# 2-Power.net
KiCad netlist of a schematic drawn in Altium Designer
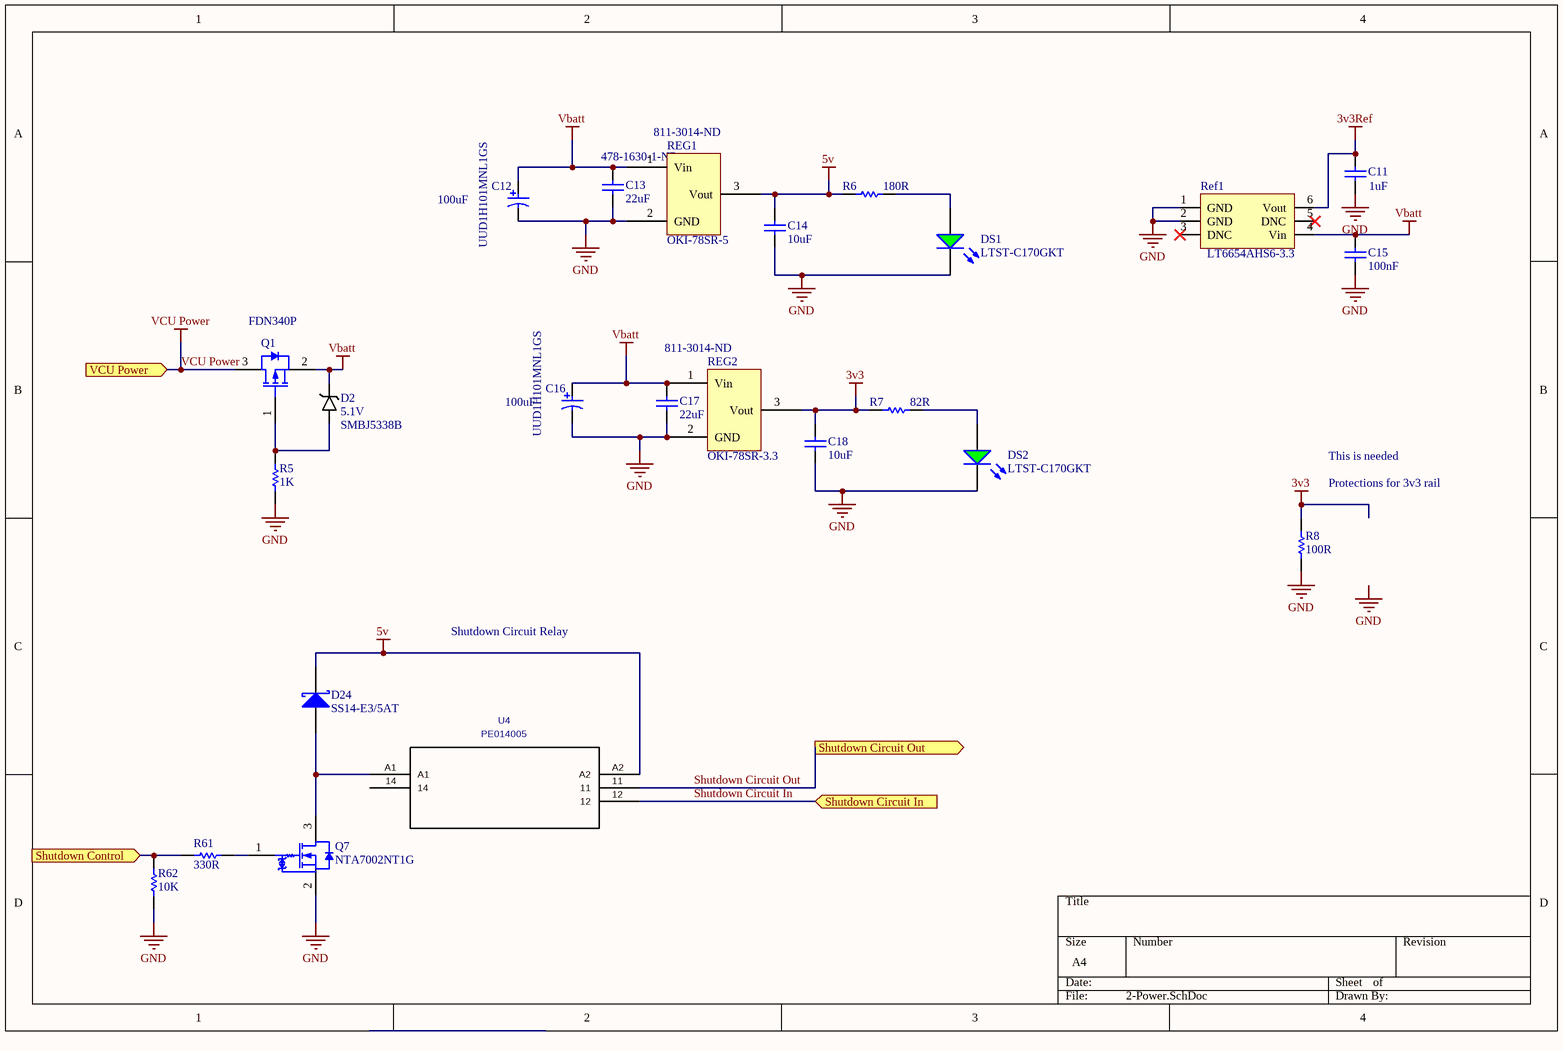
[diagram p0: 2-Power.SchDoc]

(export (version "E")
  (design (tool "Eeschema 10.0.6"))
  (components
    (comp (ref "C11")
      (value "1uF")
      (footprint "1608[0603]")
      (description "Capacitor")
      (fields
        (field (name "MANUFACTURER") "Murata Electronics North America")
        (field (name "MANUFACTURER PART NUMBER") "GRM188R61E105KA12D")
      )
      (libsource (lib "Miscellaneous Devices") (part "Cap"))
    )
    (comp (ref "C12")
      (value "UUD1H101MNL1GS")
      (footprint "NIC-CAPA2-8X10_V")
      (fields (field (name "MANUFACTURER") "Nichicon") (field (name "TOLERANCE") "±20%"))
      (libsource (lib "Altium Content Vault") (part "NIC-CAP-P-2"))
    )
    (comp (ref "C13")
      (value "22uF")
      (footprint "C1210_M")
      (description "Capacitor")
      (fields
        (field (name "MANUFACTURER") "Yageo")
        (field (name "MANUFACTURER PART NUMBER") "CC1210MKX5R8BB226")
        (field (name "SUPPLIER PART NUMBER 1") "478-1630-1-ND")
      )
      (libsource (lib "Miscellaneous Devices") (part "Cap"))
    )
    (comp (ref "C14")
      (value "10uF")
      (footprint "C1210_M")
      (description "Capacitor")
      (fields
        (field (name "MANUFACTURER") "Yageo")
        (field (name "MANUFACTURER PART NUMBER") "CC1210ZKY5V8BB106")
      )
      (libsource (lib "Miscellaneous Devices") (part "Cap"))
    )
    (comp (ref "C15")
      (value "100nF")
      (footprint "1608[0603]")
      (description "Capacitor")
      (fields
        (field (name "MANUFACTURER") "Yageo")
        (field (name "MANUFACTURER PART NUMBER") "CC0603KRX7R9BB104")
      )
      (libsource (lib "Miscellaneous Devices") (part "Cap"))
    )
    (comp (ref "C16")
      (value "UUD1H101MNL1GS")
      (footprint "NIC-CAPA2-8X10_V")
      (fields (field (name "MANUFACTURER") "Nichicon") (field (name "TOLERANCE") "±20%"))
      (libsource (lib "Altium Content Vault") (part "NIC-CAP-P-2"))
    )
    (comp (ref "C17")
      (value "22uF")
      (footprint "C1210_M")
      (description "Capacitor")
      (fields
        (field (name "MANUFACTURER") "Yageo")
        (field (name "MANUFACTURER PART NUMBER") "CC1210MKX5R8BB226")
      )
      (libsource (lib "Miscellaneous Devices") (part "Cap"))
    )
    (comp (ref "C18")
      (value "10uF")
      (footprint "C1210_M")
      (description "Capacitor")
      (fields
        (field (name "MANUFACTURER") "Yageo")
        (field (name "MANUFACTURER PART NUMBER") "CC1210ZKY5V8BB106")
      )
      (libsource (lib "Miscellaneous Devices") (part "Cap"))
    )
    (comp (ref "D2")
      (value "Zener Diode, 5.1V, 5W SMBJ5338B")
      (footprint "DO-214AA (SMB)")
      (fields
        (field (name "POWER") "5W")
        (field (name "REVERSE VOLTAGE") "5.1V")
        (field (name "PART NUMBER") "SMBJ5338B")
      )
      (libsource (lib "VCU Library") (part "Zener Diode, 5.1V, 5W SMBJ5338B"))
    )
    (comp (ref "D24")
      (value "SS14-E3/5AT")
      (footprint "VISH-DO-214AC-2_V")
      (fields (field (name "MANUFACTURER") "Vishay Semiconductor"))
      (libsource (lib "Altium Content Vault") (part "VISH-DSKY_A1K2-2"))
    )
    (comp (ref "DS1")
      (value "LTST-C170GKT")
      (footprint "LTST-C170GKT_V")
      (description "LED Uni-Color Green, 100 mW, 120 mA, -55 to 85 degC, 2-Pin SMD, RoHS, Tape and Reel")
      (fields (field (name "MANUFACTURER") "Lite-On"))
      (libsource (lib "Altium Content Vault") (part "LED-GREEN-AK-2"))
    )
    (comp (ref "DS2")
      (value "LTST-C170GKT")
      (footprint "LTST-C170GKT_V")
      (description "LED Uni-Color Green, 100 mW, 120 mA, -55 to 85 degC, 2-Pin SMD, RoHS, Tape and Reel")
      (fields (field (name "MANUFACTURER") "Lite-On"))
      (libsource (lib "Altium Content Vault") (part "LED-GREEN-AK-2"))
    )
    (comp (ref "Q1")
      (value "FDN340P")
      (footprint "FAIR-SSOT3L-3_V")
      (fields (field (name "MANUFACTURER") "Fairchild Semiconductor"))
      (libsource (lib "Altium Content Vault") (part "PEMOS-GSD-3"))
    )
    (comp (ref "Q7")
      (value "NTA7002NT1G")
      (footprint "ONSC-SC-75-3-463-01_V")
      (fields (field (name "MANUFACTURER") "On Semiconductor"))
      (libsource (lib "Altium Content Vault") (part "ONSC-NMOS-G1S2D3-3_D"))
    )
    (comp (ref "R5")
      (value "1K")
      (footprint "1608[0603]")
      (description "Resistor")
      (fields
        (field (name "MANUFACTURER") "Panasonic Electronic Components")
        (field (name "MANUFACTURER PART NUMBER") "ERJ-PA3F1001V")
      )
      (libsource (lib "Miscellaneous Devices") (part "Res1"))
    )
    (comp (ref "R6")
      (value "180R")
      (footprint "1608[0603]")
      (description "Resistor")
      (fields
        (field (name "MANUFACTURER") "Yageo")
        (field (name "MANUFACTURER PART NUMBER") "RC0603JR-07180RL")
      )
      (libsource (lib "Miscellaneous Devices") (part "Res1"))
    )
    (comp (ref "R7")
      (value "82R")
      (footprint "1608[0603]")
      (description "Resistor")
      (fields
        (field (name "MANUFACTURER") "Yageo")
        (field (name "MANUFACTURER PART NUMBER") "RC0603JR-0782RL")
      )
      (libsource (lib "Miscellaneous Devices") (part "Res1"))
    )
    (comp (ref "R8")
      (value "100R")
      (footprint "RESC1206(3216)_M")
      (description "100R 0.25W 5% 1206 (3216 Metric)  SMD")
      (fields (field (name "TOLERANCE") "5 %") (field (name "POWER") "0.25 W"))
      (libsource (lib "Altium Content Vault") (part "RES"))
    )
    (comp (ref "R61")
      (value "330R")
      (footprint "1608[0603]")
      (description "Resistor")
      (fields
        (field (name "MANUFACTURER") "Panasonic Electronic Components")
        (field (name "MANUFACTURER PART NUMBER") "ERJ-PA3F1001V")
      )
      (libsource (lib "Miscellaneous Devices") (part "Res1"))
    )
    (comp (ref "R62")
      (value "10K")
      (footprint "1608[0603]")
      (description "Resistor")
      (fields
        (field (name "MANUFACTURER") "Panasonic Electronic Components")
        (field (name "MANUFACTURER PART NUMBER") "ERJ-PA3F1001V")
      )
      (libsource (lib "Miscellaneous Devices") (part "Res1"))
    )
    (comp (ref "Ref1")
      (value "LT6654AHS6-3.3")
      (footprint "TSOT-23 S6")
      (fields
        (field (name "DIGIKEY PART NUMBER") "LT6654AHS6-3.3#TRMPBFCT-ND")
        (field (name "MANUFACTURER") "Linear Technology")
        (field (name "TOLERANCE") "±0.05%")
      )
      (libsource (lib "VCU Library") (part "LT6654AHS6-3.3"))
    )
    (comp (ref "REG1")
      (value "OKI-78SR-5")
      (footprint "OKI-78SR-5/1.5-W - Horizontal")
      (description "5V DCDC")
      (fields
        (field (name "SUPPLIER PART NUMBER 2") "811-3014-ND")
        (field (name "MANUFACTURER") "Murata Power Solutions Inc.")
        (field (name "MANUFACTURER PART NUMBER") "OKI-78SR-3.3/1.5-W36H-C")
      )
      (libsource (lib "FE Schem Lib") (part "OKI-78SR-5"))
    )
    (comp (ref "REG2")
      (value "OKI-78SR-3.3")
      (footprint "Reg - TH, 3 pin, 100 mil Pitch, VTL")
      (description "3.3V DCDC")
      (fields
        (field (name "SUPPLIER PART NUMBER 2") "811-3014-ND")
        (field (name "MANUFACTURER") "Murata Power Solutions Inc.")
        (field (name "MANUFACTURER PART NUMBER") "OKI-78SR-3.3/1.5-W36H-C")
      )
      (libsource (lib "FE Schem Lib") (part "OKI-78SR-5"))
    )
    (comp (ref "U4")
      (value "PE014005")
      (footprint "PE014005")
      (fields (field (name "COPYRIGHT") "Copyright (C) 2021 Ultra Librarian. All rights reserved."))
      (libsource (lib "AltiumV15") (part "PE014005"))
    )
  )
  (nets
    (net (code "1") (name "/Shutdown Circuit In") (class "Default")
      (node (ref "U4") (pin "12") (pinfunction "12_12") (pintype "passive"))
    )
    (net (code "2") (name "/Shutdown Circuit Out") (class "Default")
      (node (ref "U4") (pin "11") (pinfunction "11_11") (pintype "passive"))
    )
    (net (code "3") (name "/Shutdown Control") (class "Default")
      (node (ref "R61") (pin "2") (pinfunction "2_2") (pintype "passive"))
      (node (ref "R62") (pin "2") (pinfunction "2_2") (pintype "passive"))
    )
    (net (code "4") (name "3v3") (class "Default")
      (node (ref "C18") (pin "2") (pinfunction "2_2") (pintype "passive"))
      (node (ref "R7") (pin "1") (pinfunction "1_1") (pintype "passive"))
      (node (ref "R8") (pin "2") (pinfunction "2_2") (pintype "passive"))
      (node (ref "REG2") (pin "3") (pinfunction "Vout_3") (pintype "passive"))
    )
    (net (code "5") (name "3v3Ref") (class "Default")
      (node (ref "C11") (pin "2") (pinfunction "2_2") (pintype "passive"))
      (node (ref "Ref1") (pin "6") (pinfunction "Vout_6") (pintype "passive"))
    )
    (net (code "6") (name "5v") (class "Default")
      (node (ref "C14") (pin "2") (pinfunction "2_2") (pintype "passive"))
      (node (ref "D24") (pin "2") (pinfunction "K_2") (pintype "passive"))
      (node (ref "R6") (pin "1") (pinfunction "1_1") (pintype "passive"))
      (node (ref "REG1") (pin "3") (pinfunction "Vout_3") (pintype "passive"))
      (node (ref "U4") (pin "A2") (pinfunction "A2_A2") (pintype "passive"))
    )
    (net (code "7") (name "GND") (class "Default")
      (node (ref "C11") (pin "1") (pinfunction "1_1") (pintype "passive"))
      (node (ref "C12") (pin "2") (pinfunction "2_2") (pintype "passive"))
      (node (ref "C13") (pin "1") (pinfunction "1_1") (pintype "passive"))
      (node (ref "C14") (pin "1") (pinfunction "1_1") (pintype "passive"))
      (node (ref "C15") (pin "1") (pinfunction "1_1") (pintype "passive"))
      (node (ref "C16") (pin "2") (pinfunction "2_2") (pintype "passive"))
      (node (ref "C17") (pin "1") (pinfunction "1_1") (pintype "passive"))
      (node (ref "C18") (pin "1") (pinfunction "1_1") (pintype "passive"))
      (node (ref "DS1") (pin "2") (pinfunction "K_2") (pintype "passive"))
      (node (ref "DS2") (pin "2") (pinfunction "K_2") (pintype "passive"))
      (node (ref "Q7") (pin "2") (pinfunction "S_2") (pintype "passive"))
      (node (ref "R5") (pin "1") (pinfunction "1_1") (pintype "passive"))
      (node (ref "R62") (pin "1") (pinfunction "1_1") (pintype "passive"))
      (node (ref "R8") (pin "1") (pinfunction "1_1") (pintype "passive"))
      (node (ref "REG1") (pin "2") (pinfunction "GND_2") (pintype "passive"))
      (node (ref "REG2") (pin "2") (pinfunction "GND_2") (pintype "passive"))
      (node (ref "Ref1") (pin "1") (pinfunction "GND_1") (pintype "passive"))
      (node (ref "Ref1") (pin "2") (pinfunction "GND_2") (pintype "passive"))
    )
    (net (code "8") (name "Net-(D2-2)") (class "Default")
      (node (ref "D2") (pin "A") (pinfunction "2_A") (pintype "passive"))
      (node (ref "Q1") (pin "1") (pinfunction "GATE_1") (pintype "passive"))
      (node (ref "R5") (pin "2") (pinfunction "2_2") (pintype "passive"))
    )
    (net (code "9") (name "Net-(D24-A)") (class "Default")
      (node (ref "D24") (pin "1") (pinfunction "A_1") (pintype "passive"))
      (node (ref "Q7") (pin "3") (pinfunction "D_3") (pintype "passive"))
      (node (ref "U4") (pin "A1") (pinfunction "A1_A1") (pintype "passive"))
    )
    (net (code "10") (name "Net-(DS1-A)") (class "Default")
      (node (ref "DS1") (pin "1") (pinfunction "A_1") (pintype "passive"))
      (node (ref "R6") (pin "2") (pinfunction "2_2") (pintype "passive"))
    )
    (net (code "11") (name "Net-(DS2-A)") (class "Default")
      (node (ref "DS2") (pin "1") (pinfunction "A_1") (pintype "passive"))
      (node (ref "R7") (pin "2") (pinfunction "2_2") (pintype "passive"))
    )
    (net (code "12") (name "Net-(Q7-G)") (class "Default")
      (node (ref "Q7") (pin "1") (pinfunction "G_1") (pintype "passive"))
      (node (ref "R61") (pin "1") (pinfunction "1_1") (pintype "passive"))
    )
    (net (code "13") (name "VCU Power") (class "Default")
      (node (ref "Q1") (pin "3") (pinfunction "DRAIN_3") (pintype "passive"))
    )
    (net (code "14") (name "Vbatt") (class "Default")
      (node (ref "C12") (pin "1") (pinfunction "1_1") (pintype "passive"))
      (node (ref "C13") (pin "2") (pinfunction "2_2") (pintype "passive"))
      (node (ref "C15") (pin "2") (pinfunction "2_2") (pintype "passive"))
      (node (ref "C16") (pin "1") (pinfunction "1_1") (pintype "passive"))
      (node (ref "C17") (pin "2") (pinfunction "2_2") (pintype "passive"))
      (node (ref "D2") (pin "K") (pinfunction "1_K") (pintype "passive"))
      (node (ref "Q1") (pin "2") (pinfunction "SOURCE_2") (pintype "passive"))
      (node (ref "REG1") (pin "1") (pinfunction "Vin_1") (pintype "passive"))
      (node (ref "REG2") (pin "1") (pinfunction "Vin_1") (pintype "passive"))
      (node (ref "Ref1") (pin "4") (pinfunction "Vin_4") (pintype "passive"))
    )
    (net (code "15") (name "unconnected-(Ref1-DNC-Pad3)") (class "Default")
      (node (ref "Ref1") (pin "3") (pinfunction "DNC_3") (pintype "passive+no_connect"))
    )
    (net (code "16") (name "unconnected-(Ref1-DNC-Pad5)") (class "Default")
      (node (ref "Ref1") (pin "5") (pinfunction "DNC_5") (pintype "passive+no_connect"))
    )
    (net (code "17") (name "unconnected-(U4-Pad14)") (class "Default")
      (node (ref "U4") (pin "14") (pinfunction "14_14") (pintype "passive"))
    )
  )
)
